# card.net
KiCad netlist of a schematic drawn in EAGLE
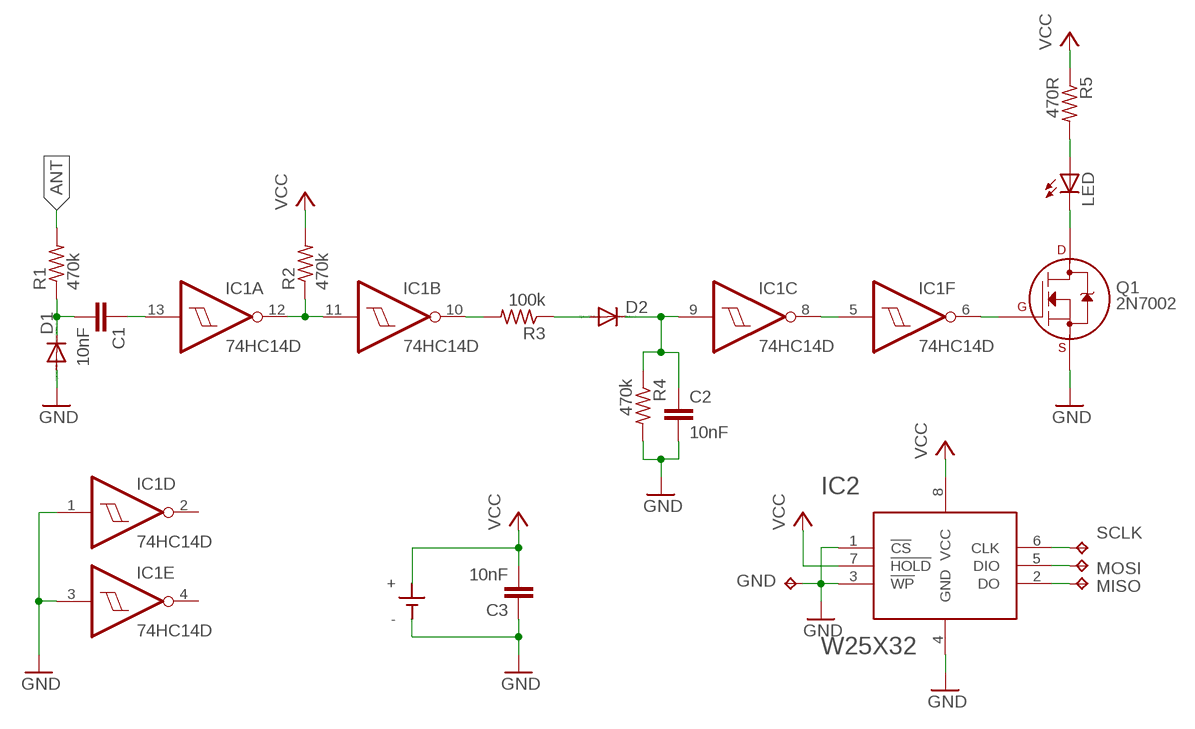
[diagram p0: schematic, sheet 1]

(export (version "E")
  (design (tool "Eeschema 10.0.6"))
  (components
    (comp (ref "BAT")
      (value "KB3003")
      (footprint "eagle-import:KB3003")
      (libsource (lib "eagle-import") (part "KB3003"))
    )
    (comp (ref "C1")
      (value "10nF")
      (footprint "eagle-import:C1206K")
      (libsource (lib "eagle-import") (part "C-EUC1206K"))
    )
    (comp (ref "C2")
      (value "10nF")
      (footprint "eagle-import:C1206K")
      (libsource (lib "eagle-import") (part "C-EUC1206K"))
    )
    (comp (ref "C3")
      (value "10nF")
      (footprint "eagle-import:C1206K")
      (libsource (lib "eagle-import") (part "C-EUC1206K"))
    )
    (comp (ref "D1")
      (value "DIODE-MINIMELF")
      (footprint "eagle-import:MINIMELF")
      (libsource (lib "eagle-import") (part "DIODE-MINIMELF"))
    )
    (comp (ref "D2")
      (value "DIODE-MINIMELF")
      (footprint "eagle-import:MINIMELF")
      (libsource (lib "eagle-import") (part "DIODE-MINIMELF"))
    )
    (comp (ref "GND")
      (value "TPB1,27")
      (footprint "eagle-import:B1,27")
      (libsource (lib "eagle-import") (part "TPB1,27"))
    )
    (comp (ref "IC1")
      (value "74HC14D")
      (footprint "eagle-import:SO14")
      (libsource (lib "eagle-import") (part "7414DHC"))
    )
    (comp (ref "IC2")
      (value "W25X32")
      (footprint "eagle-import:SOIC8")
      (libsource (lib "eagle-import") (part "W25X32"))
    )
    (comp (ref "LED")
      (value "LEDCHIPLED_1206")
      (footprint "eagle-import:CHIPLED_1206")
      (libsource (lib "eagle-import") (part "LEDCHIPLED_1206"))
    )
    (comp (ref "MISO")
      (value "TPB1,27")
      (footprint "eagle-import:B1,27")
      (libsource (lib "eagle-import") (part "TPB1,27"))
    )
    (comp (ref "MOSI")
      (value "TPB1,27")
      (footprint "eagle-import:B1,27")
      (libsource (lib "eagle-import") (part "TPB1,27"))
    )
    (comp (ref "Q1")
      (value "2N7002")
      (footprint "eagle-import:SOT-23")
      (libsource (lib "eagle-import") (part "2N700_SOT230"))
    )
    (comp (ref "R1")
      (value "470k")
      (footprint "eagle-import:M1206")
      (libsource (lib "eagle-import") (part "R-US_M1206"))
    )
    (comp (ref "R2")
      (value "470k")
      (footprint "eagle-import:M1206")
      (libsource (lib "eagle-import") (part "R-US_M1206"))
    )
    (comp (ref "R3")
      (value "100k")
      (footprint "eagle-import:M1206")
      (libsource (lib "eagle-import") (part "R-US_M1206"))
    )
    (comp (ref "R4")
      (value "470k")
      (footprint "eagle-import:M1206")
      (libsource (lib "eagle-import") (part "R-US_M1206"))
    )
    (comp (ref "R5")
      (value "470R")
      (footprint "eagle-import:M1206")
      (libsource (lib "eagle-import") (part "R-US_M1206"))
    )
    (comp (ref "SCLK")
      (value "TPB1,27")
      (footprint "eagle-import:B1,27")
      (libsource (lib "eagle-import") (part "TPB1,27"))
    )
  )
  (nets
    (net (code "1") (name "ANT") (class "Default")
      (node (ref "R1") (pin "2") (pinfunction "2_2") (pintype "passive"))
    )
    (net (code "2") (name "GND") (class "Default")
      (node (ref "BAT") (pin "-") (pinfunction "-_-") (pintype "power_in"))
      (node (ref "C2") (pin "2") (pinfunction "2_2") (pintype "passive"))
      (node (ref "C3") (pin "1") (pinfunction "1_1") (pintype "passive"))
      (node (ref "D1") (pin "A") (pinfunction "A_A") (pintype "passive"))
      (node (ref "GND") (pin "TP") (pinfunction "TP_TP") (pintype "input"))
      (node (ref "IC1") (pin "1") (pinfunction "I_1") (pintype "input"))
      (node (ref "IC1") (pin "3") (pinfunction "I_3") (pintype "input"))
      (node (ref "IC2") (pin "1") (pinfunction "~{CS}_1") (pintype "input"))
      (node (ref "IC2") (pin "3") (pinfunction "~{WP}_3") (pintype "input"))
      (node (ref "IC2") (pin "4") (pinfunction "GND_4") (pintype "power_in"))
      (node (ref "Q1") (pin "2") (pinfunction "S_2") (pintype "bidirectional"))
      (node (ref "R4") (pin "2") (pinfunction "2_2") (pintype "passive"))
    )
    (net (code "3") (name "Net-(C1-Pad2)") (class "Default")
      (node (ref "C1") (pin "2") (pinfunction "2_2") (pintype "passive"))
      (node (ref "D1") (pin "C") (pinfunction "C_C") (pintype "passive"))
      (node (ref "R1") (pin "1") (pinfunction "1_1") (pintype "passive"))
    )
    (net (code "4") (name "Net-(D2-PadA)") (class "Default")
      (node (ref "D2") (pin "A") (pinfunction "A_A") (pintype "passive"))
      (node (ref "R3") (pin "1") (pinfunction "1_1") (pintype "passive"))
    )
    (net (code "5") (name "Net-(IC1A-I)") (class "Default")
      (node (ref "C1") (pin "1") (pinfunction "1_1") (pintype "passive"))
      (node (ref "IC1") (pin "13") (pinfunction "I_13") (pintype "input"))
    )
    (net (code "6") (name "Net-(IC1A-O)") (class "Default")
      (node (ref "IC1") (pin "11") (pinfunction "I_11") (pintype "input"))
      (node (ref "IC1") (pin "12") (pinfunction "O_12") (pintype "output"))
      (node (ref "R2") (pin "1") (pinfunction "1_1") (pintype "passive"))
    )
    (net (code "7") (name "Net-(IC1B-O)") (class "Default")
      (node (ref "IC1") (pin "10") (pinfunction "O_10") (pintype "output"))
      (node (ref "R3") (pin "2") (pinfunction "2_2") (pintype "passive"))
    )
    (net (code "8") (name "Net-(IC1C-I)") (class "Default")
      (node (ref "C2") (pin "1") (pinfunction "1_1") (pintype "passive"))
      (node (ref "D2") (pin "C") (pinfunction "C_C") (pintype "passive"))
      (node (ref "IC1") (pin "9") (pinfunction "I_9") (pintype "input"))
      (node (ref "R4") (pin "1") (pinfunction "1_1") (pintype "passive"))
    )
    (net (code "9") (name "Net-(IC1C-O)") (class "Default")
      (node (ref "IC1") (pin "5") (pinfunction "I_5") (pintype "input"))
      (node (ref "IC1") (pin "8") (pinfunction "O_8") (pintype "output"))
    )
    (net (code "10") (name "Net-(IC1F-O)") (class "Default")
      (node (ref "IC1") (pin "6") (pinfunction "O_6") (pintype "output"))
      (node (ref "Q1") (pin "1") (pinfunction "G_1") (pintype "tri_state"))
    )
    (net (code "11") (name "Net-(IC2-CLK)") (class "Default")
      (node (ref "IC2") (pin "6") (pinfunction "CLK_6") (pintype "input"))
      (node (ref "SCLK") (pin "TP") (pinfunction "TP_TP") (pintype "input"))
    )
    (net (code "12") (name "Net-(IC2-DIO)") (class "Default")
      (node (ref "IC2") (pin "5") (pinfunction "DIO_5") (pintype "input"))
      (node (ref "MOSI") (pin "TP") (pinfunction "TP_TP") (pintype "input"))
    )
    (net (code "13") (name "Net-(IC2-DO)") (class "Default")
      (node (ref "IC2") (pin "2") (pinfunction "DO_2") (pintype "output"))
      (node (ref "MISO") (pin "TP") (pinfunction "TP_TP") (pintype "input"))
    )
    (net (code "14") (name "Net-(LED-PadA)") (class "Default")
      (node (ref "LED") (pin "A") (pinfunction "A_A") (pintype "passive"))
      (node (ref "R5") (pin "2") (pinfunction "2_2") (pintype "passive"))
    )
    (net (code "15") (name "Net-(Q1-D)") (class "Default")
      (node (ref "LED") (pin "C") (pinfunction "C_C") (pintype "passive"))
      (node (ref "Q1") (pin "3") (pinfunction "D_3") (pintype "bidirectional"))
    )
    (net (code "16") (name "VCC") (class "Default")
      (node (ref "BAT") (pin "+@1") (pinfunction "+_+@1") (pintype "power_in"))
      (node (ref "BAT") (pin "+@2") (pinfunction "+_+@2") (pintype "power_in"))
      (node (ref "C3") (pin "2") (pinfunction "2_2") (pintype "passive"))
      (node (ref "IC2") (pin "7") (pinfunction "~{HOLD}_7") (pintype "input"))
      (node (ref "IC2") (pin "8") (pinfunction "VCC_8") (pintype "power_in"))
      (node (ref "R2") (pin "2") (pinfunction "2_2") (pintype "passive"))
      (node (ref "R5") (pin "1") (pinfunction "1_1") (pintype "passive"))
    )
    (net (code "17") (name "unconnected-(IC1D-O-Pad2)") (class "Default")
      (node (ref "IC1") (pin "2") (pinfunction "O_2") (pintype "output"))
    )
    (net (code "18") (name "unconnected-(IC1E-O-Pad4)") (class "Default")
      (node (ref "IC1") (pin "4") (pinfunction "O_4") (pintype "output"))
    )
  )
)
